# FD_Capacitance_Sensor_v08.net
KiCad netlist of a schematic drawn in EAGLE
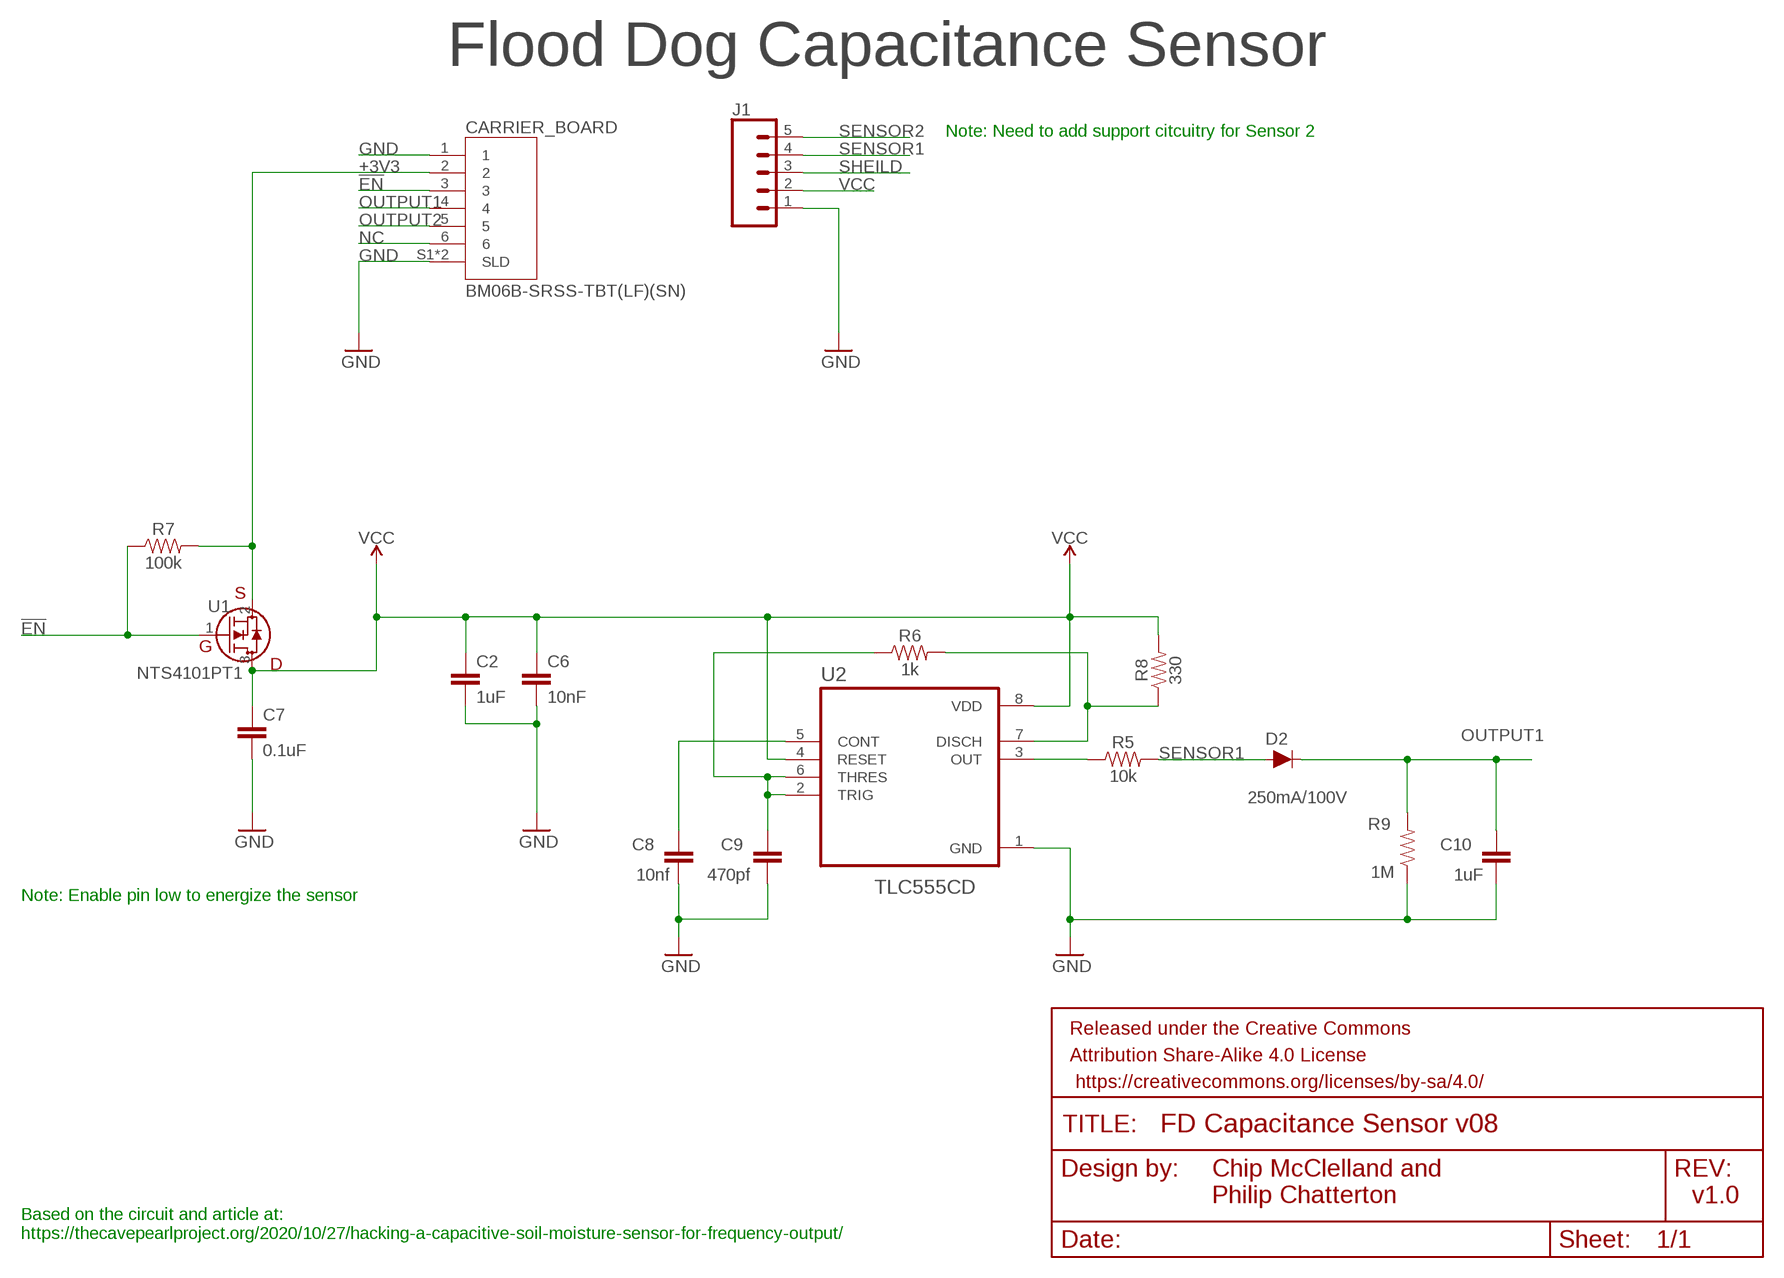
[diagram p0: schematic, sheet 1]

(export (version "E")
  (design (tool "Eeschema 10.0.6"))
  (components
    (comp (ref "C2")
      (value "1uF")
      (footprint "eagle-import:0805@1")
      (fields (field (name "HOUSEPART") "yes") (field (name "MPN") "MF-CAP-0805-1uF"))
      (libsource (lib "eagle-import") (part "CAP-MF-1UF-0805"))
    )
    (comp (ref "C6")
      (value "10nF")
      (footprint "eagle-import:0805@1")
      (fields (field (name "HOUSEPART") "NO") (field (name "MPN") "C0805X103K1RAC3316"))
      (libsource (lib "eagle-import") (part "CAP-10NF-0805"))
    )
    (comp (ref "C7")
      (value "0.1uF")
      (footprint "eagle-import:0805@1")
      (fields (field (name "HOUSEPART") "YES") (field (name "MPN") "MF-CAP-0805-0.1uF"))
      (libsource (lib "eagle-import") (part "CAP-MF-0.1UF-0805"))
    )
    (comp (ref "C8")
      (value "10nf")
      (footprint "eagle-import:C0805")
      (libsource (lib "eagle-import") (part "C-EUC0805"))
    )
    (comp (ref "C9")
      (value "470pf")
      (footprint "eagle-import:C0805")
      (libsource (lib "eagle-import") (part "C-EUC0805"))
    )
    (comp (ref "C10")
      (value "1uF")
      (footprint "eagle-import:C0805")
      (libsource (lib "eagle-import") (part "C-EUC0805"))
    )
    (comp (ref "CARRIER_BOARD")
      (value "BM06B-SRSS-TBT(LF)(SN)")
      (footprint "eagle-import:JST_BM06B-SRSS-TB(LF)(SN)")
      (libsource (lib "eagle-import") (part "BM06B-SRSS-TBT(LF)(SN)"))
    )
    (comp (ref "D2")
      (value "250mA/100V")
      (footprint "eagle-import:SOD-323")
      (fields (field (name "MPN") "BAS16HT1G"))
      (libsource (lib "eagle-import") (part "DIODE-BAS16J"))
    )
    (comp (ref "FRAME1")
      (value "FRAME-LETTERNO_PACKAGE")
      (footprint "eagle-import:DUMMY")
      (fields (field (name "DESIGNER") "Nobody"))
      (libsource (lib "eagle-import") (part "FRAME-LETTERNO_PACKAGE"))
    )
    (comp (ref "J1")
      (value "CONN_05SCREW")
      (footprint "eagle-import:SCREWTERMINAL-3.5MM-5")
      (libsource (lib "eagle-import") (part "CONN_05SCREW"))
    )
    (comp (ref "R5")
      (value "10k")
      (footprint "eagle-import:0805")
      (fields (field (name "MPN") "MF-RES-0805-10K"))
      (libsource (lib "eagle-import") (part "RESISTOR-MF-10K-0805"))
    )
    (comp (ref "R6")
      (value "1k")
      (footprint "eagle-import:0805")
      (fields (field (name "HOUSEPART") "YES") (field (name "MPN") "MF-RES-0805-1K"))
      (libsource (lib "eagle-import") (part "RESISTOR-MF-1K-0805"))
    )
    (comp (ref "R7")
      (value "100k")
      (footprint "eagle-import:0805")
      (fields (field (name "MPN") "MF-RES-0805-100K") (field (name "MPN_1") "MF-RES-0805-100K"))
      (libsource (lib "eagle-import") (part "RESISTOR-MF-100K-0805"))
    )
    (comp (ref "R8")
      (value "330")
      (footprint "eagle-import:0805")
      (fields (field (name "HOUSEPART") "YES") (field (name "MPN") "MF-RES-0805-330"))
      (libsource (lib "eagle-import") (part "RESISTOR-MF-330-0805"))
    )
    (comp (ref "R9")
      (value "1M")
      (footprint "eagle-import:0805")
      (fields (field (name "HOUSEPART") "YES") (field (name "MPN") "MF-RES-0805-1K"))
      (libsource (lib "eagle-import") (part "RESISTOR-MF-1K-0805"))
    )
    (comp (ref "U1")
      (value "NTS4101PT1")
      (footprint "eagle-import:SOT_101PT1_ONS")
      (libsource (lib "eagle-import") (part "NTS4101PT1"))
    )
    (comp (ref "U2")
      (value "TLC555CD")
      (footprint "eagle-import:SOIC127P599X175-8N")
      (fields (field (name "DIGI-KEY_PART_NUMBER") "296-52992-ND") (field (name "MF") "Texas Instruments"))
      (libsource (lib "eagle-import") (part "TLC555CD"))
    )
  )
  (nets
    (net (code "1") (name "/+3V3") (class "Default")
      (node (ref "CARRIER_BOARD") (pin "2") (pinfunction "2_2") (pintype "passive"))
      (node (ref "R7") (pin "2") (pinfunction "2_2") (pintype "passive"))
      (node (ref "U1") (pin "2") (pinfunction "S_2") (pintype "passive"))
    )
    (net (code "2") (name "/NC") (class "Default")
      (node (ref "CARRIER_BOARD") (pin "6") (pinfunction "6_6") (pintype "passive"))
    )
    (net (code "3") (name "/OUTPUT1") (class "Default")
      (node (ref "C10") (pin "2") (pinfunction "2_2") (pintype "passive"))
      (node (ref "CARRIER_BOARD") (pin "4") (pinfunction "4_4") (pintype "passive"))
      (node (ref "D2") (pin "C") (pinfunction "C_C") (pintype "passive"))
      (node (ref "R9") (pin "2") (pinfunction "2_2") (pintype "passive"))
    )
    (net (code "4") (name "/OUTPUT2") (class "Default")
      (node (ref "CARRIER_BOARD") (pin "5") (pinfunction "5_5") (pintype "passive"))
    )
    (net (code "5") (name "/SENSOR1") (class "Default")
      (node (ref "D2") (pin "A") (pinfunction "A_A") (pintype "passive"))
      (node (ref "J1") (pin "4") (pinfunction "4_4") (pintype "passive"))
      (node (ref "R5") (pin "2") (pinfunction "2_2") (pintype "passive"))
    )
    (net (code "6") (name "/SENSOR2") (class "Default")
      (node (ref "J1") (pin "5") (pinfunction "5_5") (pintype "passive"))
    )
    (net (code "7") (name "/SHEILD") (class "Default")
      (node (ref "J1") (pin "3") (pinfunction "3_3") (pintype "passive"))
    )
    (net (code "8") (name "/~{EN}") (class "Default")
      (node (ref "CARRIER_BOARD") (pin "3") (pinfunction "3_3") (pintype "passive"))
      (node (ref "R7") (pin "1") (pinfunction "1_1") (pintype "passive"))
      (node (ref "U1") (pin "1") (pinfunction "G_1") (pintype "passive"))
    )
    (net (code "9") (name "GND") (class "Default")
      (node (ref "C10") (pin "1") (pinfunction "1_1") (pintype "passive"))
      (node (ref "C2") (pin "2") (pinfunction "2_2") (pintype "passive"))
      (node (ref "C6") (pin "2") (pinfunction "2_2") (pintype "passive"))
      (node (ref "C7") (pin "2") (pinfunction "2_2") (pintype "passive"))
      (node (ref "C8") (pin "1") (pinfunction "1_1") (pintype "passive"))
      (node (ref "C9") (pin "1") (pinfunction "1_1") (pintype "passive"))
      (node (ref "CARRIER_BOARD") (pin "1") (pinfunction "1_1") (pintype "passive"))
      (node (ref "CARRIER_BOARD") (pin "S1") (pinfunction "SLD_S1") (pintype "passive"))
      (node (ref "CARRIER_BOARD") (pin "S2") (pinfunction "SLD_S2") (pintype "passive"))
      (node (ref "J1") (pin "1") (pinfunction "1_1") (pintype "passive"))
      (node (ref "R9") (pin "1") (pinfunction "1_1") (pintype "passive"))
      (node (ref "U2") (pin "1") (pinfunction "GND_1") (pintype "power_in"))
    )
    (net (code "10") (name "Net-(U2-CONT)") (class "Default")
      (node (ref "C8") (pin "2") (pinfunction "2_2") (pintype "passive"))
      (node (ref "U2") (pin "5") (pinfunction "CONT_5") (pintype "input"))
    )
    (net (code "11") (name "Net-(U2-DISCH)") (class "Default")
      (node (ref "R6") (pin "2") (pinfunction "2_2") (pintype "passive"))
      (node (ref "R8") (pin "1") (pinfunction "1_1") (pintype "passive"))
      (node (ref "U2") (pin "7") (pinfunction "DISCH_7") (pintype "output"))
    )
    (net (code "12") (name "Net-(U2-OUT)") (class "Default")
      (node (ref "R5") (pin "1") (pinfunction "1_1") (pintype "passive"))
      (node (ref "U2") (pin "3") (pinfunction "OUT_3") (pintype "output"))
    )
    (net (code "13") (name "Net-(U2-THRES)") (class "Default")
      (node (ref "C9") (pin "2") (pinfunction "2_2") (pintype "passive"))
      (node (ref "R6") (pin "1") (pinfunction "1_1") (pintype "passive"))
      (node (ref "U2") (pin "2") (pinfunction "TRIG_2") (pintype "input"))
      (node (ref "U2") (pin "6") (pinfunction "THRES_6") (pintype "input"))
    )
    (net (code "14") (name "VCC") (class "Default")
      (node (ref "C2") (pin "1") (pinfunction "1_1") (pintype "passive"))
      (node (ref "C6") (pin "1") (pinfunction "1_1") (pintype "passive"))
      (node (ref "C7") (pin "1") (pinfunction "1_1") (pintype "passive"))
      (node (ref "J1") (pin "2") (pinfunction "2_2") (pintype "passive"))
      (node (ref "R8") (pin "2") (pinfunction "2_2") (pintype "passive"))
      (node (ref "U1") (pin "3") (pinfunction "D_3") (pintype "passive"))
      (node (ref "U2") (pin "4") (pinfunction "RESET_4") (pintype "input"))
      (node (ref "U2") (pin "8") (pinfunction "VDD_8") (pintype "power_in"))
    )
  )
)
